# Mounting_PCB_B.net
KiCad netlist of a schematic drawn in Altium Designer
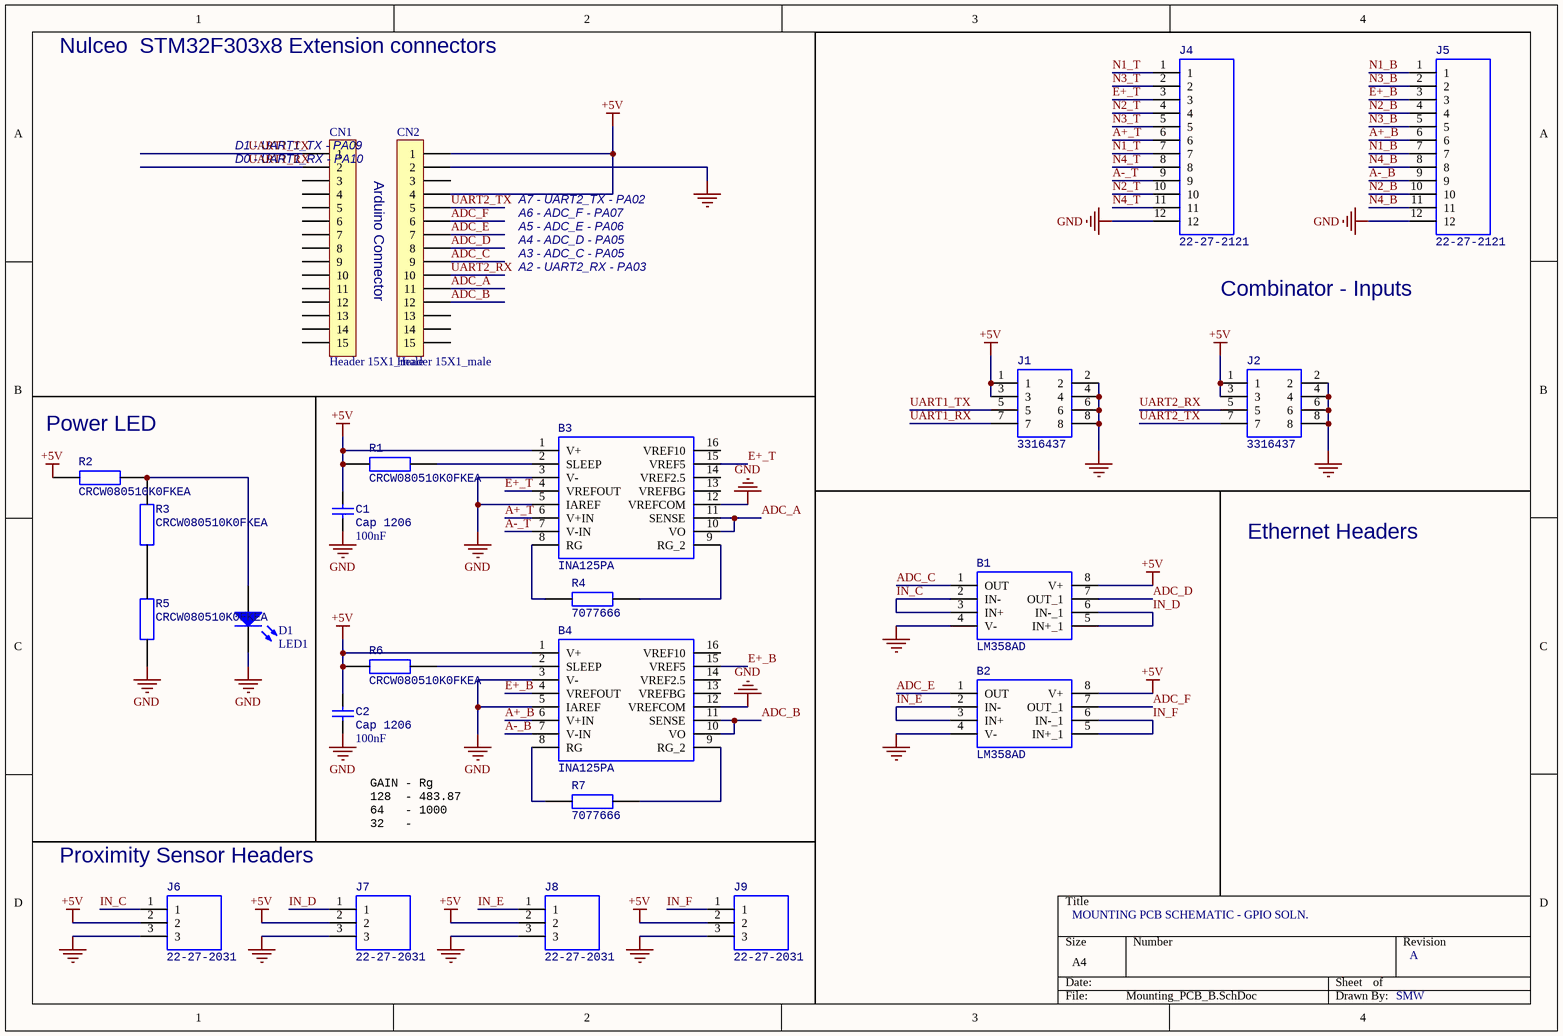
[diagram p0: Mounting_PCB_B.SchDoc]

(export (version "E")
  (design (tool "Eeschema 10.0.6"))
  (components
    (comp (ref "B1")
      (value "LM358AD")
      (footprint "SOIC127P600X175-8N")
      (description "LM358AD, Dual Operational Amplifier 1.1MHz 5 to 28V, 8-Pin SO")
      (fields (field (name "RS PART NUMBER") "1657542"))
      (libsource (lib "LM358AD") (part "LM358AD"))
    )
    (comp (ref "B2")
      (value "LM358AD")
      (footprint "SOIC127P600X175-8N")
      (description "LM358AD, Dual Operational Amplifier 1.1MHz 5 to 28V, 8-Pin SO")
      (fields (field (name "RS PART NUMBER") "1657542"))
      (libsource (lib "LM358AD") (part "LM358AD"))
    )
    (comp (ref "B3")
      (value "INA125PA")
      (footprint "DIP254P762X508-16")
      (description "Instrumentation Amplifier with Precision Voltage Reference")
      (fields (field (name "RS PART NUMBER") "2521593P"))
      (libsource (lib "INA125PA") (part "INA125PA"))
    )
    (comp (ref "B4")
      (value "INA125PA")
      (footprint "DIP254P762X508-16")
      (description "Instrumentation Amplifier with Precision Voltage Reference")
      (fields (field (name "RS PART NUMBER") "2521593P"))
      (libsource (lib "INA125PA") (part "INA125PA"))
    )
    (comp (ref "C1")
      (value "Cap 1206")
      (footprint "C1206")
      (description "Capacitor (Semiconductor SIM Model)")
      (fields (field (name "ALTIUM_VALUE") "100nF") (field (name "PUBLISHER") "Altium Limited"))
      (libsource (lib "Miscellaneous Devices") (part "Cap Semi"))
    )
    (comp (ref "C2")
      (value "Cap 1206")
      (footprint "C1206")
      (description "Capacitor (Semiconductor SIM Model)")
      (fields (field (name "ALTIUM_VALUE") "100nF") (field (name "PUBLISHER") "Altium Limited"))
      (libsource (lib "Miscellaneous Devices") (part "Cap Semi"))
    )
    (comp (ref "CN1")
      (value "Header 15X1_male")
      (footprint "HDR_1x15_2R54_V_F")
      (description "Header, 10-Pin, Single row,female")
      (fields (field (name "PUBLISHER") "Altium Limited"))
      (libsource (lib "MB1180") (part "Header 15X1_Female_1"))
    )
    (comp (ref "CN2")
      (value "Header 15X1_male")
      (footprint "HDR_1x15_2R54_V_F")
      (description "Header, 10-Pin, Single row,female")
      (fields (field (name "PUBLISHER") "Altium Limited"))
      (libsource (lib "") (part "Header 15X1_Female_1_1"))
    )
    (comp (ref "D1")
      (value "LED1")
      (footprint "L0603")
      (description "Typical RED GaAs LED")
      (fields (field (name "PUBLISHER") "Altium Limited"))
      (libsource (lib "Miscellaneous Devices") (part "LED1"))
    )
    (comp (ref "J1") (value "3316437") (footprint "3316437") (libsource (lib "3316437") (part "3316437")))
    (comp (ref "J2") (value "3316437") (footprint "3316437") (libsource (lib "3316437") (part "3316437")))
    (comp (ref "J4")
      (value "22-27-2121")
      (footprint "HDRV12W64P0X254_1X12_3048X580X1170P")
      (fields (field (name "RS PART NUMBER") "1707108"))
      (libsource (lib "22-27-2121") (part "22-27-2121"))
    )
    (comp (ref "J5")
      (value "22-27-2121")
      (footprint "HDRV12W64P0X254_1X12_3048X580X1170P")
      (fields (field (name "RS PART NUMBER") "1707108"))
      (libsource (lib "22-27-2121") (part "22-27-2121"))
    )
    (comp (ref "J6")
      (value "22-27-2031")
      (footprint "SHDR3W64P0X254_1X3_762X580X1170P")
      (fields (field (name "RS PART NUMBER") "1707102"))
      (libsource (lib "22-27-2031") (part "22-27-2031"))
    )
    (comp (ref "J7")
      (value "22-27-2031")
      (footprint "SHDR3W64P0X254_1X3_762X580X1170P")
      (fields (field (name "RS PART NUMBER") "1707102"))
      (libsource (lib "22-27-2031") (part "22-27-2031"))
    )
    (comp (ref "J8")
      (value "22-27-2031")
      (footprint "SHDR3W64P0X254_1X3_762X580X1170P")
      (fields (field (name "RS PART NUMBER") "1707102"))
      (libsource (lib "22-27-2031") (part "22-27-2031"))
    )
    (comp (ref "J9")
      (value "22-27-2031")
      (footprint "SHDR3W64P0X254_1X3_762X580X1170P")
      (fields (field (name "RS PART NUMBER") "1707102"))
      (libsource (lib "22-27-2031") (part "22-27-2031"))
    )
    (comp (ref "R1")
      (value "CRCW080510K0FKEA")
      (footprint "RESC2012X50N")
      (fields (field (name "RS PART NUMBER") "1694499"))
      (libsource (lib "CRCW080510K0FKEA") (part "CRCW080510K0FKEA"))
    )
    (comp (ref "R2")
      (value "CRCW080510K0FKEA")
      (footprint "RESC2012X50N")
      (fields (field (name "RS PART NUMBER") "1694499"))
      (libsource (lib "CRCW080510K0FKEA") (part "CRCW080510K0FKEA"))
    )
    (comp (ref "R3")
      (value "CRCW080510K0FKEA")
      (footprint "RESC2012X50N")
      (fields (field (name "RS PART NUMBER") "1694499"))
      (libsource (lib "CRCW080510K0FKEA") (part "CRCW080510K0FKEA"))
    )
    (comp (ref "R4")
      (value "7077666")
      (footprint "RESAD1550W58L630D230")
      (description "RS Pro RS Series Axial Carbon Resistor 1k 5% 0.25W -500  +350ppm/C")
      (libsource (lib "7077666") (part "7077666"))
    )
    (comp (ref "R5")
      (value "CRCW080510K0FKEA")
      (footprint "RESC2012X50N")
      (fields (field (name "RS PART NUMBER") "1694499"))
      (libsource (lib "CRCW080510K0FKEA") (part "CRCW080510K0FKEA"))
    )
    (comp (ref "R6")
      (value "CRCW080510K0FKEA")
      (footprint "RESC2012X50N")
      (fields (field (name "RS PART NUMBER") "1694499"))
      (libsource (lib "CRCW080510K0FKEA") (part "CRCW080510K0FKEA"))
    )
    (comp (ref "R7")
      (value "7077666")
      (footprint "RESAD1550W58L630D230")
      (description "RS Pro RS Series Axial Carbon Resistor 1k 5% 0.25W -500  +350ppm/C")
      (libsource (lib "7077666") (part "7077666"))
    )
  )
  (nets
    (net (code "1") (name "+5V") (class "Default")
      (node (ref "B1") (pin "8") (pinfunction "V+_8") (pintype "passive"))
      (node (ref "B2") (pin "8") (pinfunction "V+_8") (pintype "passive"))
      (node (ref "B3") (pin "1") (pinfunction "V+_1") (pintype "passive"))
      (node (ref "B4") (pin "1") (pinfunction "V+_1") (pintype "passive"))
      (node (ref "C1") (pin "2") (pinfunction "2_2") (pintype "passive"))
      (node (ref "C2") (pin "2") (pinfunction "2_2") (pintype "passive"))
      (node (ref "CN2") (pin "1") (pinfunction "1_1") (pintype "passive"))
      (node (ref "CN2") (pin "4") (pinfunction "4_4") (pintype "passive"))
      (node (ref "J1") (pin "1") (pinfunction "1_1") (pintype "passive"))
      (node (ref "J1") (pin "3") (pinfunction "3_3") (pintype "passive"))
      (node (ref "J2") (pin "1") (pinfunction "1_1") (pintype "passive"))
      (node (ref "J2") (pin "3") (pinfunction "3_3") (pintype "passive"))
      (node (ref "J6") (pin "2") (pinfunction "2_2") (pintype "passive"))
      (node (ref "J7") (pin "2") (pinfunction "2_2") (pintype "passive"))
      (node (ref "J8") (pin "2") (pinfunction "2_2") (pintype "passive"))
      (node (ref "J9") (pin "2") (pinfunction "2_2") (pintype "passive"))
      (node (ref "R1") (pin "1") (pinfunction "1_1") (pintype "passive"))
      (node (ref "R2") (pin "1") (pinfunction "1_1") (pintype "passive"))
      (node (ref "R6") (pin "1") (pinfunction "1_1") (pintype "passive"))
    )
    (net (code "2") (name "/A+_B") (class "Default")
      (node (ref "B4") (pin "6") (pinfunction "V+IN_6") (pintype "passive"))
      (node (ref "J5") (pin "6") (pinfunction "6_6") (pintype "passive"))
    )
    (net (code "3") (name "/A+_T") (class "Default")
      (node (ref "B3") (pin "6") (pinfunction "V+IN_6") (pintype "passive"))
      (node (ref "J4") (pin "6") (pinfunction "6_6") (pintype "passive"))
    )
    (net (code "4") (name "/A-_B") (class "Default")
      (node (ref "B4") (pin "7") (pinfunction "V-IN_7") (pintype "passive"))
      (node (ref "J5") (pin "9") (pinfunction "9_9") (pintype "passive"))
    )
    (net (code "5") (name "/A-_T") (class "Default")
      (node (ref "B3") (pin "7") (pinfunction "V-IN_7") (pintype "passive"))
      (node (ref "J4") (pin "9") (pinfunction "9_9") (pintype "passive"))
    )
    (net (code "6") (name "/ADC_A") (class "Default")
      (node (ref "B3") (pin "10") (pinfunction "VO_10") (pintype "passive"))
      (node (ref "B3") (pin "11") (pinfunction "SENSE_11") (pintype "passive"))
      (node (ref "CN2") (pin "11") (pinfunction "11_11") (pintype "passive"))
    )
    (net (code "7") (name "/ADC_B") (class "Default")
      (node (ref "B4") (pin "10") (pinfunction "VO_10") (pintype "passive"))
      (node (ref "B4") (pin "11") (pinfunction "SENSE_11") (pintype "passive"))
      (node (ref "CN2") (pin "12") (pinfunction "12_12") (pintype "passive"))
    )
    (net (code "8") (name "/ADC_C") (class "Default")
      (node (ref "B1") (pin "1") (pinfunction "OUT_1") (pintype "passive"))
      (node (ref "CN2") (pin "9") (pinfunction "9_9") (pintype "passive"))
    )
    (net (code "9") (name "/ADC_D") (class "Default")
      (node (ref "B1") (pin "7") (pinfunction "OUT_1_7") (pintype "passive"))
      (node (ref "CN2") (pin "8") (pinfunction "8_8") (pintype "passive"))
    )
    (net (code "10") (name "/ADC_E") (class "Default")
      (node (ref "B2") (pin "1") (pinfunction "OUT_1") (pintype "passive"))
      (node (ref "CN2") (pin "7") (pinfunction "7_7") (pintype "passive"))
    )
    (net (code "11") (name "/ADC_F") (class "Default")
      (node (ref "B2") (pin "7") (pinfunction "OUT_1_7") (pintype "passive"))
      (node (ref "CN2") (pin "6") (pinfunction "6_6") (pintype "passive"))
    )
    (net (code "12") (name "/E+_B") (class "Default")
      (node (ref "B4") (pin "15") (pinfunction "VREF5_15") (pintype "passive"))
      (node (ref "B4") (pin "4") (pinfunction "VREFOUT_4") (pintype "passive"))
      (node (ref "J5") (pin "3") (pinfunction "3_3") (pintype "passive"))
    )
    (net (code "13") (name "/E+_T") (class "Default")
      (node (ref "B3") (pin "15") (pinfunction "VREF5_15") (pintype "passive"))
      (node (ref "B3") (pin "4") (pinfunction "VREFOUT_4") (pintype "passive"))
      (node (ref "J4") (pin "3") (pinfunction "3_3") (pintype "passive"))
    )
    (net (code "14") (name "/IN_C") (class "Default")
      (node (ref "B1") (pin "2") (pinfunction "IN-_2") (pintype "passive"))
      (node (ref "B1") (pin "3") (pinfunction "IN+_3") (pintype "passive"))
      (node (ref "J6") (pin "1") (pinfunction "1_1") (pintype "passive"))
    )
    (net (code "15") (name "/IN_D") (class "Default")
      (node (ref "B1") (pin "5") (pinfunction "IN+_1_5") (pintype "passive"))
      (node (ref "B1") (pin "6") (pinfunction "IN-_1_6") (pintype "passive"))
      (node (ref "J7") (pin "1") (pinfunction "1_1") (pintype "passive"))
    )
    (net (code "16") (name "/IN_E") (class "Default")
      (node (ref "B2") (pin "2") (pinfunction "IN-_2") (pintype "passive"))
      (node (ref "B2") (pin "3") (pinfunction "IN+_3") (pintype "passive"))
      (node (ref "J8") (pin "1") (pinfunction "1_1") (pintype "passive"))
    )
    (net (code "17") (name "/IN_F") (class "Default")
      (node (ref "B2") (pin "5") (pinfunction "IN+_1_5") (pintype "passive"))
      (node (ref "B2") (pin "6") (pinfunction "IN-_1_6") (pintype "passive"))
      (node (ref "J9") (pin "1") (pinfunction "1_1") (pintype "passive"))
    )
    (net (code "18") (name "/N1_B") (class "Default")
      (node (ref "J5") (pin "1") (pinfunction "1_1") (pintype "passive"))
      (node (ref "J5") (pin "7") (pinfunction "7_7") (pintype "passive"))
    )
    (net (code "19") (name "/N1_T") (class "Default")
      (node (ref "J4") (pin "1") (pinfunction "1_1") (pintype "passive"))
      (node (ref "J4") (pin "7") (pinfunction "7_7") (pintype "passive"))
    )
    (net (code "20") (name "/N2_B") (class "Default")
      (node (ref "J5") (pin "10") (pinfunction "10_10") (pintype "passive"))
      (node (ref "J5") (pin "4") (pinfunction "4_4") (pintype "passive"))
    )
    (net (code "21") (name "/N2_T") (class "Default")
      (node (ref "J4") (pin "10") (pinfunction "10_10") (pintype "passive"))
      (node (ref "J4") (pin "4") (pinfunction "4_4") (pintype "passive"))
    )
    (net (code "22") (name "/N3_B") (class "Default")
      (node (ref "J5") (pin "2") (pinfunction "2_2") (pintype "passive"))
      (node (ref "J5") (pin "5") (pinfunction "5_5") (pintype "passive"))
    )
    (net (code "23") (name "/N3_T") (class "Default")
      (node (ref "J4") (pin "2") (pinfunction "2_2") (pintype "passive"))
      (node (ref "J4") (pin "5") (pinfunction "5_5") (pintype "passive"))
    )
    (net (code "24") (name "/N4_B") (class "Default")
      (node (ref "J5") (pin "11") (pinfunction "11_11") (pintype "passive"))
      (node (ref "J5") (pin "8") (pinfunction "8_8") (pintype "passive"))
    )
    (net (code "25") (name "/N4_T") (class "Default")
      (node (ref "J4") (pin "11") (pinfunction "11_11") (pintype "passive"))
      (node (ref "J4") (pin "8") (pinfunction "8_8") (pintype "passive"))
    )
    (net (code "26") (name "/UART1_RX") (class "Default")
      (node (ref "CN1") (pin "2") (pinfunction "2_2") (pintype "passive"))
      (node (ref "J1") (pin "7") (pinfunction "7_7") (pintype "passive"))
    )
    (net (code "27") (name "/UART1_TX") (class "Default")
      (node (ref "CN1") (pin "1") (pinfunction "1_1") (pintype "passive"))
      (node (ref "J1") (pin "5") (pinfunction "5_5") (pintype "passive"))
    )
    (net (code "28") (name "/UART2_RX") (class "Default")
      (node (ref "CN2") (pin "10") (pinfunction "10_10") (pintype "passive"))
      (node (ref "J2") (pin "5") (pinfunction "5_5") (pintype "passive"))
    )
    (net (code "29") (name "/UART2_TX") (class "Default")
      (node (ref "CN2") (pin "5") (pinfunction "5_5") (pintype "passive"))
      (node (ref "J2") (pin "7") (pinfunction "7_7") (pintype "passive"))
    )
    (net (code "30") (name "GND") (class "Default")
      (node (ref "B1") (pin "4") (pinfunction "V-_4") (pintype "passive"))
      (node (ref "B2") (pin "4") (pinfunction "V-_4") (pintype "passive"))
      (node (ref "B3") (pin "12") (pinfunction "VREFCOM_12") (pintype "passive"))
      (node (ref "B3") (pin "3") (pinfunction "V-_3") (pintype "passive"))
      (node (ref "B3") (pin "5") (pinfunction "IAREF_5") (pintype "passive"))
      (node (ref "B4") (pin "12") (pinfunction "VREFCOM_12") (pintype "passive"))
      (node (ref "B4") (pin "3") (pinfunction "V-_3") (pintype "passive"))
      (node (ref "B4") (pin "5") (pinfunction "IAREF_5") (pintype "passive"))
      (node (ref "C1") (pin "1") (pinfunction "1_1") (pintype "passive"))
      (node (ref "C2") (pin "1") (pinfunction "1_1") (pintype "passive"))
      (node (ref "CN2") (pin "2") (pinfunction "2_2") (pintype "passive"))
      (node (ref "D1") (pin "2") (pinfunction "K_2") (pintype "passive"))
      (node (ref "J1") (pin "2") (pinfunction "2_2") (pintype "passive"))
      (node (ref "J1") (pin "4") (pinfunction "4_4") (pintype "passive"))
      (node (ref "J1") (pin "6") (pinfunction "6_6") (pintype "passive"))
      (node (ref "J1") (pin "8") (pinfunction "8_8") (pintype "passive"))
      (node (ref "J2") (pin "2") (pinfunction "2_2") (pintype "passive"))
      (node (ref "J2") (pin "4") (pinfunction "4_4") (pintype "passive"))
      (node (ref "J2") (pin "6") (pinfunction "6_6") (pintype "passive"))
      (node (ref "J2") (pin "8") (pinfunction "8_8") (pintype "passive"))
      (node (ref "J4") (pin "12") (pinfunction "12_12") (pintype "passive"))
      (node (ref "J5") (pin "12") (pinfunction "12_12") (pintype "passive"))
      (node (ref "J6") (pin "3") (pinfunction "3_3") (pintype "passive"))
      (node (ref "J7") (pin "3") (pinfunction "3_3") (pintype "passive"))
      (node (ref "J8") (pin "3") (pinfunction "3_3") (pintype "passive"))
      (node (ref "J9") (pin "3") (pinfunction "3_3") (pintype "passive"))
      (node (ref "R5") (pin "1") (pinfunction "1_1") (pintype "passive"))
    )
    (net (code "31") (name "Net-(B3-RG)") (class "Default")
      (node (ref "B3") (pin "8") (pinfunction "RG_8") (pintype "passive"))
      (node (ref "R4") (pin "1") (pinfunction "1_1") (pintype "passive"))
    )
    (net (code "32") (name "Net-(B3-RG_2)") (class "Default")
      (node (ref "B3") (pin "9") (pinfunction "RG_2_9") (pintype "passive"))
      (node (ref "R4") (pin "2") (pinfunction "2_2") (pintype "passive"))
    )
    (net (code "33") (name "Net-(B3-SLEEP)") (class "Default")
      (node (ref "B3") (pin "2") (pinfunction "SLEEP_2") (pintype "passive"))
      (node (ref "R1") (pin "2") (pinfunction "2_2") (pintype "passive"))
    )
    (net (code "34") (name "Net-(B4-RG)") (class "Default")
      (node (ref "B4") (pin "8") (pinfunction "RG_8") (pintype "passive"))
      (node (ref "R7") (pin "1") (pinfunction "1_1") (pintype "passive"))
    )
    (net (code "35") (name "Net-(B4-RG_2)") (class "Default")
      (node (ref "B4") (pin "9") (pinfunction "RG_2_9") (pintype "passive"))
      (node (ref "R7") (pin "2") (pinfunction "2_2") (pintype "passive"))
    )
    (net (code "36") (name "Net-(B4-SLEEP)") (class "Default")
      (node (ref "B4") (pin "2") (pinfunction "SLEEP_2") (pintype "passive"))
      (node (ref "R6") (pin "2") (pinfunction "2_2") (pintype "passive"))
    )
    (net (code "37") (name "Net-(D1-A)") (class "Default")
      (node (ref "D1") (pin "1") (pinfunction "A_1") (pintype "passive"))
      (node (ref "R2") (pin "2") (pinfunction "2_2") (pintype "passive"))
      (node (ref "R3") (pin "2") (pinfunction "2_2") (pintype "passive"))
    )
    (net (code "38") (name "Net-(R3-Pad1)") (class "Default")
      (node (ref "R3") (pin "1") (pinfunction "1_1") (pintype "passive"))
      (node (ref "R5") (pin "2") (pinfunction "2_2") (pintype "passive"))
    )
    (net (code "39") (name "unconnected-(B3-VREF2.5-Pad14)") (class "Default")
      (node (ref "B3") (pin "14") (pinfunction "VREF2.5_14") (pintype "passive"))
    )
    (net (code "40") (name "unconnected-(B3-VREF10-Pad16)") (class "Default")
      (node (ref "B3") (pin "16") (pinfunction "VREF10_16") (pintype "passive"))
    )
    (net (code "41") (name "unconnected-(B3-VREFBG-Pad13)") (class "Default")
      (node (ref "B3") (pin "13") (pinfunction "VREFBG_13") (pintype "passive"))
    )
    (net (code "42") (name "unconnected-(B4-VREF2.5-Pad14)") (class "Default")
      (node (ref "B4") (pin "14") (pinfunction "VREF2.5_14") (pintype "passive"))
    )
    (net (code "43") (name "unconnected-(B4-VREF10-Pad16)") (class "Default")
      (node (ref "B4") (pin "16") (pinfunction "VREF10_16") (pintype "passive"))
    )
    (net (code "44") (name "unconnected-(B4-VREFBG-Pad13)") (class "Default")
      (node (ref "B4") (pin "13") (pinfunction "VREFBG_13") (pintype "passive"))
    )
    (net (code "45") (name "unconnected-(CN1-Pad3)") (class "Default")
      (node (ref "CN1") (pin "3") (pinfunction "3_3") (pintype "passive"))
    )
    (net (code "46") (name "unconnected-(CN1-Pad4)") (class "Default")
      (node (ref "CN1") (pin "4") (pinfunction "4_4") (pintype "passive"))
    )
    (net (code "47") (name "unconnected-(CN1-Pad5)") (class "Default")
      (node (ref "CN1") (pin "5") (pinfunction "5_5") (pintype "passive"))
    )
    (net (code "48") (name "unconnected-(CN1-Pad6)") (class "Default")
      (node (ref "CN1") (pin "6") (pinfunction "6_6") (pintype "passive"))
    )
    (net (code "49") (name "unconnected-(CN1-Pad7)") (class "Default")
      (node (ref "CN1") (pin "7") (pinfunction "7_7") (pintype "passive"))
    )
    (net (code "50") (name "unconnected-(CN1-Pad8)") (class "Default")
      (node (ref "CN1") (pin "8") (pinfunction "8_8") (pintype "passive"))
    )
    (net (code "51") (name "unconnected-(CN1-Pad9)") (class "Default")
      (node (ref "CN1") (pin "9") (pinfunction "9_9") (pintype "passive"))
    )
    (net (code "52") (name "unconnected-(CN1-Pad10)") (class "Default")
      (node (ref "CN1") (pin "10") (pinfunction "10_10") (pintype "passive"))
    )
    (net (code "53") (name "unconnected-(CN1-Pad11)") (class "Default")
      (node (ref "CN1") (pin "11") (pinfunction "11_11") (pintype "passive"))
    )
    (net (code "54") (name "unconnected-(CN1-Pad12)") (class "Default")
      (node (ref "CN1") (pin "12") (pinfunction "12_12") (pintype "passive"))
    )
    (net (code "55") (name "unconnected-(CN1-Pad13)") (class "Default")
      (node (ref "CN1") (pin "13") (pinfunction "13_13") (pintype "passive"))
    )
    (net (code "56") (name "unconnected-(CN1-Pad14)") (class "Default")
      (node (ref "CN1") (pin "14") (pinfunction "14_14") (pintype "passive"))
    )
    (net (code "57") (name "unconnected-(CN1-Pad15)") (class "Default")
      (node (ref "CN1") (pin "15") (pinfunction "15_15") (pintype "passive"))
    )
    (net (code "58") (name "unconnected-(CN2-Pad3)") (class "Default")
      (node (ref "CN2") (pin "3") (pinfunction "3_3") (pintype "passive"))
    )
    (net (code "59") (name "unconnected-(CN2-Pad13)") (class "Default")
      (node (ref "CN2") (pin "13") (pinfunction "13_13") (pintype "passive"))
    )
    (net (code "60") (name "unconnected-(CN2-Pad14)") (class "Default")
      (node (ref "CN2") (pin "14") (pinfunction "14_14") (pintype "passive"))
    )
    (net (code "61") (name "unconnected-(CN2-Pad15)") (class "Default")
      (node (ref "CN2") (pin "15") (pinfunction "15_15") (pintype "passive"))
    )
  )
)
